# DisplayTestBoard.net
KiCad netlist of a schematic drawn in EAGLE
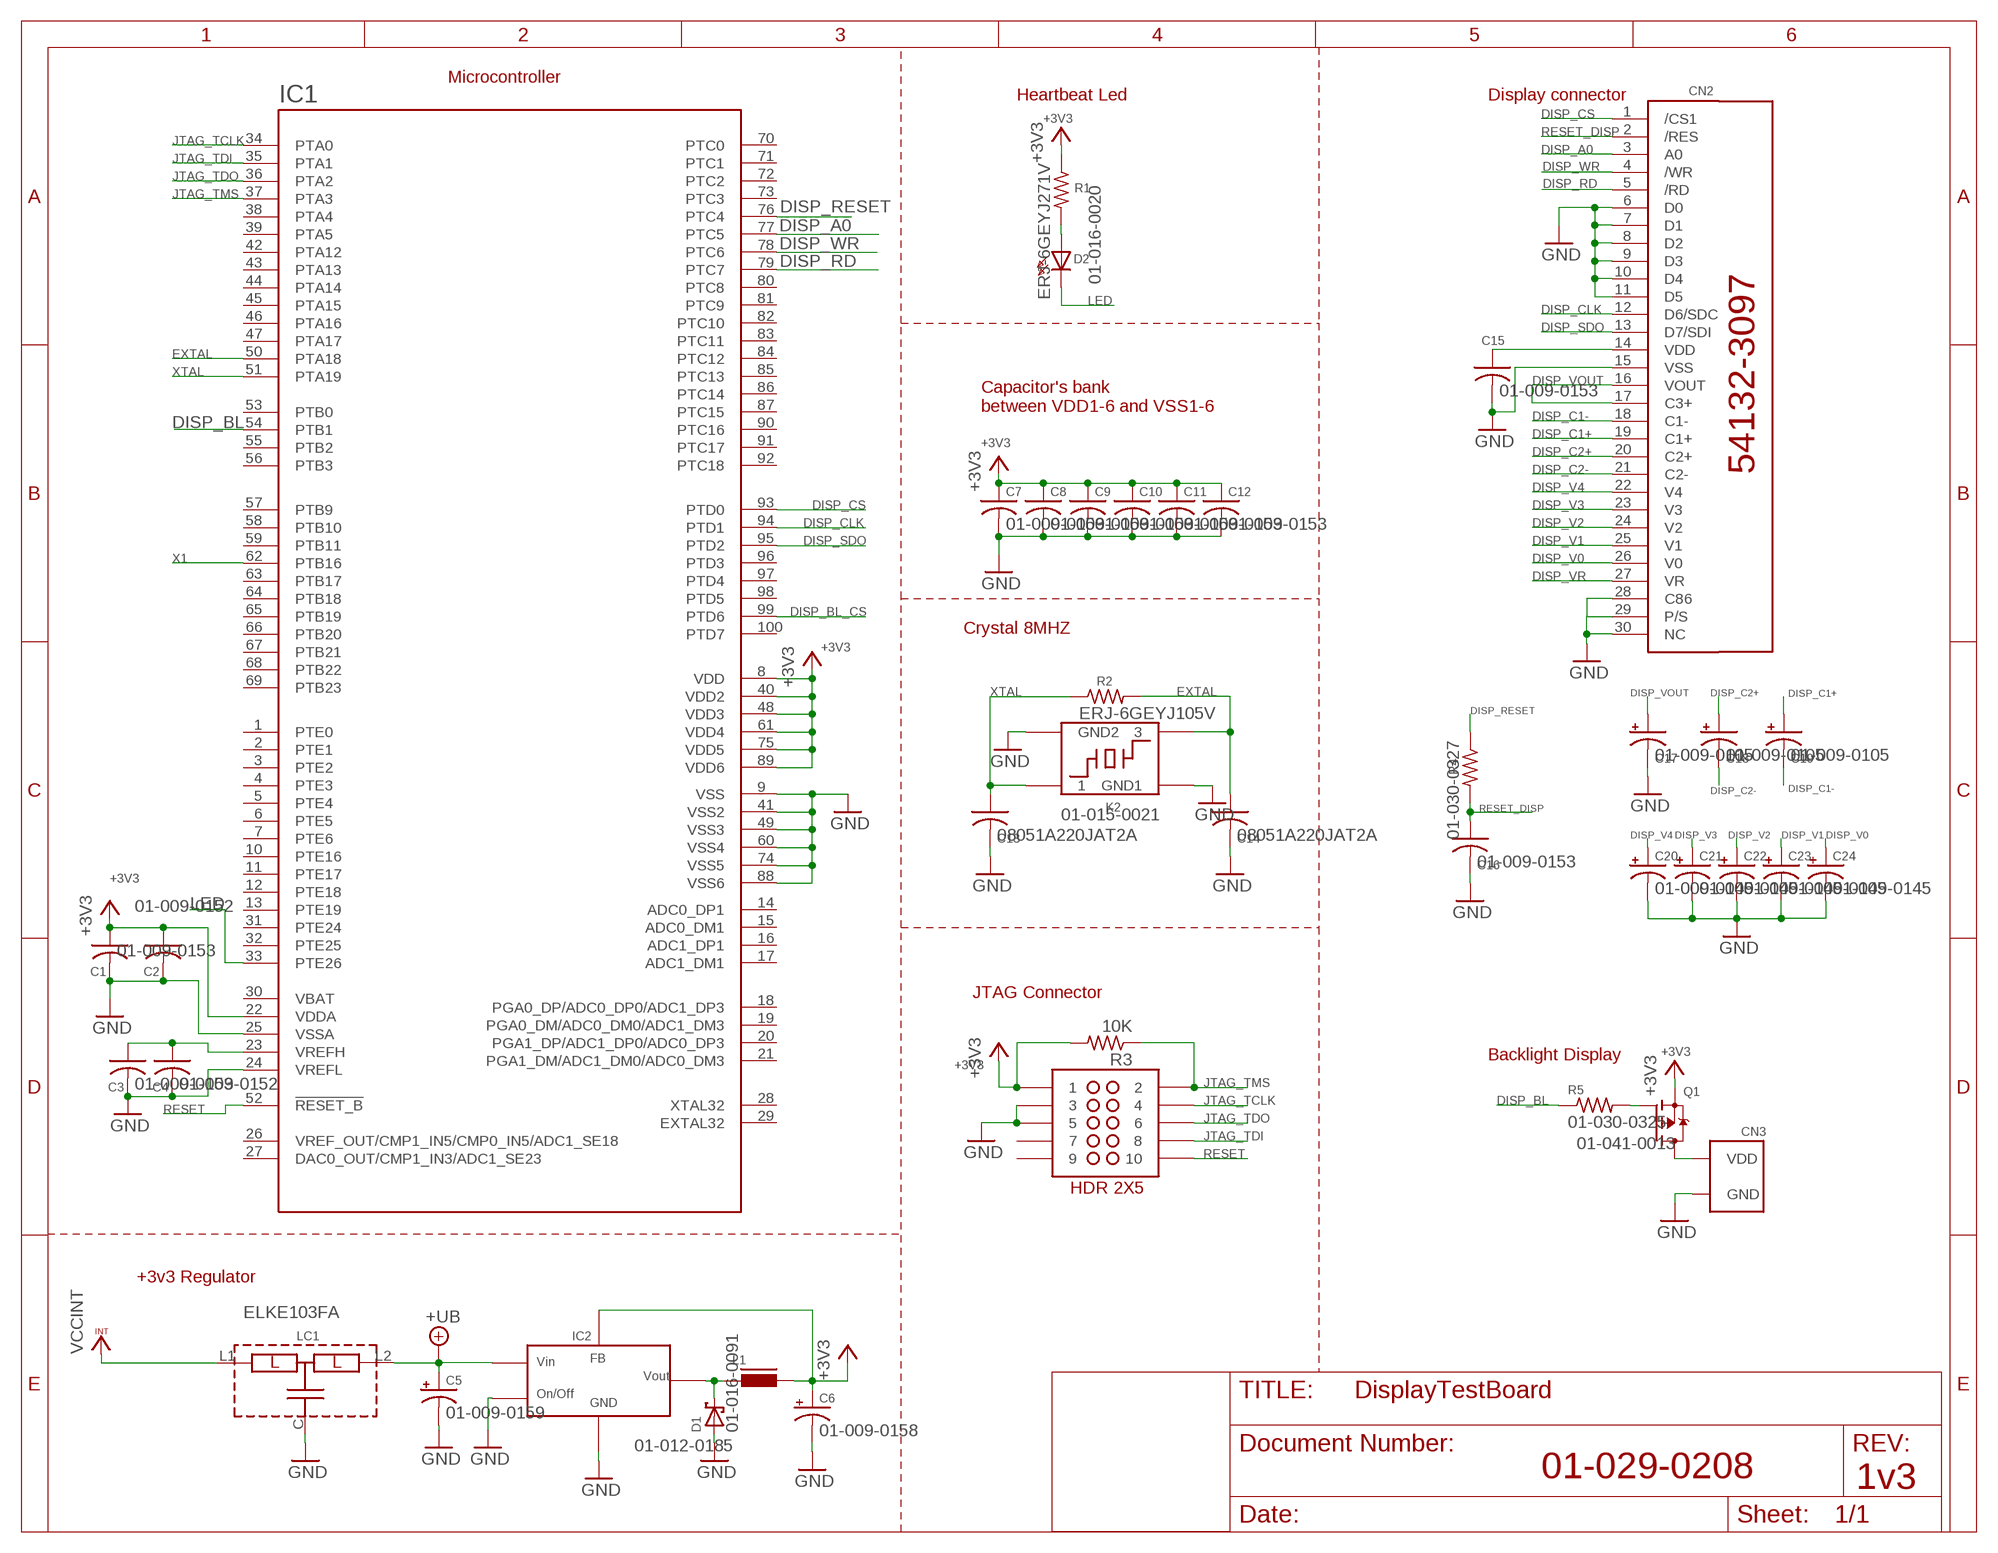
[diagram p0: schematic, sheet 1]

(export (version "E")
  (design (tool "Eeschema 10.0.6"))
  (components
    (comp (ref "C1")
      (value "01-009-0153")
      (footprint "eagle-import:C0805")
      (libsource (lib "eagle-import") (part "01-009-0153"))
    )
    (comp (ref "C2")
      (value "01-009-0152")
      (footprint "eagle-import:C0805")
      (libsource (lib "eagle-import") (part "01-009-0152"))
    )
    (comp (ref "C3")
      (value "01-009-0153")
      (footprint "eagle-import:C0805")
      (libsource (lib "eagle-import") (part "01-009-0153"))
    )
    (comp (ref "C4")
      (value "01-009-0152")
      (footprint "eagle-import:C0805")
      (libsource (lib "eagle-import") (part "01-009-0152"))
    )
    (comp (ref "C5")
      (value "01-009-0159")
      (footprint "eagle-import:PANASONIC_6.3MM")
      (libsource (lib "eagle-import") (part "01-009-0159"))
    )
    (comp (ref "C6")
      (value "01-009-0158")
      (footprint "eagle-import:PANASONIC_6.3MM")
      (libsource (lib "eagle-import") (part "01-009-0158"))
    )
    (comp (ref "C7")
      (value "01-009-0153")
      (footprint "eagle-import:C0805")
      (libsource (lib "eagle-import") (part "01-009-0153"))
    )
    (comp (ref "C8")
      (value "01-009-0153")
      (footprint "eagle-import:C0805")
      (libsource (lib "eagle-import") (part "01-009-0153"))
    )
    (comp (ref "C9")
      (value "01-009-0153")
      (footprint "eagle-import:C0805")
      (libsource (lib "eagle-import") (part "01-009-0153"))
    )
    (comp (ref "C10")
      (value "01-009-0153")
      (footprint "eagle-import:C0805")
      (libsource (lib "eagle-import") (part "01-009-0153"))
    )
    (comp (ref "C11")
      (value "01-009-0153")
      (footprint "eagle-import:C0805")
      (libsource (lib "eagle-import") (part "01-009-0153"))
    )
    (comp (ref "C12")
      (value "01-009-0153")
      (footprint "eagle-import:C0805")
      (libsource (lib "eagle-import") (part "01-009-0153"))
    )
    (comp (ref "C13")
      (value "08051A220JAT2A")
      (footprint "eagle-import:C0805")
      (libsource (lib "eagle-import") (part "08051A220JAT2A"))
    )
    (comp (ref "C14")
      (value "08051A220JAT2A")
      (footprint "eagle-import:C0805")
      (libsource (lib "eagle-import") (part "08051A220JAT2A"))
    )
    (comp (ref "C15")
      (value "01-009-0153")
      (footprint "eagle-import:C0805")
      (libsource (lib "eagle-import") (part "01-009-0153"))
    )
    (comp (ref "C16")
      (value "01-009-0153")
      (footprint "eagle-import:C0805")
      (libsource (lib "eagle-import") (part "01-009-0153"))
    )
    (comp (ref "C17")
      (value "01-009-0105")
      (footprint "eagle-import:CT3528")
      (libsource (lib "eagle-import") (part "01-009-0105"))
    )
    (comp (ref "C18")
      (value "01-009-0105")
      (footprint "eagle-import:CT3528")
      (libsource (lib "eagle-import") (part "01-009-0105"))
    )
    (comp (ref "C19")
      (value "01-009-0105")
      (footprint "eagle-import:CT3528")
      (libsource (lib "eagle-import") (part "01-009-0105"))
    )
    (comp (ref "C20")
      (value "01-009-0145")
      (footprint "eagle-import:CT3528")
      (libsource (lib "eagle-import") (part "01-009-0145"))
    )
    (comp (ref "C21")
      (value "01-009-0145")
      (footprint "eagle-import:CT3528")
      (libsource (lib "eagle-import") (part "01-009-0145"))
    )
    (comp (ref "C22")
      (value "01-009-0145")
      (footprint "eagle-import:CT3528")
      (libsource (lib "eagle-import") (part "01-009-0145"))
    )
    (comp (ref "C23")
      (value "01-009-0145")
      (footprint "eagle-import:CT3528")
      (libsource (lib "eagle-import") (part "01-009-0145"))
    )
    (comp (ref "C24")
      (value "01-009-0145")
      (footprint "eagle-import:CT3528")
      (libsource (lib "eagle-import") (part "01-009-0145"))
    )
    (comp (ref "CN2")
      (value "01-014-0371")
      (footprint "eagle-import:XF2L-3035-1")
      (libsource (lib "eagle-import") (part "01-014-0371"))
    )
    (comp (ref "CN3")
      (value "01-014-0372")
      (footprint "eagle-import:S2B-PH-K-S")
      (libsource (lib "eagle-import") (part "01-014-0372"))
    )
    (comp (ref "D1")
      (value "01-016-0091")
      (footprint "eagle-import:SOD123")
      (libsource (lib "eagle-import") (part "01-016-0091"))
    )
    (comp (ref "D2")
      (value "01-016-0020")
      (footprint "eagle-import:LED0603")
      (libsource (lib "eagle-import") (part "01-016-0020"))
    )
    (comp (ref "IC1")
      (value "01-012-0181")
      (footprint "eagle-import:LQFP100")
      (libsource (lib "eagle-import") (part "01-012-0181"))
    )
    (comp (ref "IC2")
      (value "01-012-0185")
      (footprint "eagle-import:SO08")
      (libsource (lib "eagle-import") (part "01-012-0185"))
    )
    (comp (ref "JTAG")
      (value "SAMTECSTR2X5")
      (footprint "eagle-import:SAMTECSTR2X5")
      (libsource (lib "eagle-import") (part "SAMTECSTR2X5"))
    )
    (comp (ref "K2")
      (value "01-015-0021")
      (footprint "eagle-import:XTAL")
      (libsource (lib "eagle-import") (part "01-015-0021"))
    )
    (comp (ref "L1")
      (value "01-023-0014")
      (footprint "eagle-import:SRR1260")
      (libsource (lib "eagle-import") (part "01-023-0014"))
    )
    (comp (ref "LC1")
      (value "ELKE103FA")
      (footprint "eagle-import:ELKE103FA")
      (libsource (lib "eagle-import") (part "ELKE103FA"))
    )
    (comp (ref "Q1")
      (value "01-041-0013")
      (footprint "eagle-import:SOT-23")
      (libsource (lib "eagle-import") (part "01-041-0013"))
    )
    (comp (ref "R1")
      (value "ERJ-6GEYJ271V")
      (footprint "eagle-import:M0805")
      (libsource (lib "eagle-import") (part "ERJ-6GEYJ271V"))
    )
    (comp (ref "R2")
      (value "ERJ-6GEYJ105V")
      (footprint "eagle-import:M0805")
      (libsource (lib "eagle-import") (part "ERJ-6GEYJ105V"))
    )
    (comp (ref "R3")
      (value "10K")
      (footprint "eagle-import:M0805")
      (libsource (lib "eagle-import") (part "01-030-0334"))
    )
    (comp (ref "R4")
      (value "01-030-0327")
      (footprint "eagle-import:M0805")
      (libsource (lib "eagle-import") (part "01-030-0327"))
    )
    (comp (ref "R5")
      (value "01-030-0325")
      (footprint "eagle-import:M0805")
      (libsource (lib "eagle-import") (part "01-030-0325"))
    )
  )
  (nets
    (net (code "1") (name "+3V3") (class "Default")
      (node (ref "C1") (pin "1") (pinfunction "1_1") (pintype "passive"))
      (node (ref "C10") (pin "1") (pinfunction "1_1") (pintype "passive"))
      (node (ref "C11") (pin "1") (pinfunction "1_1") (pintype "passive"))
      (node (ref "C12") (pin "1") (pinfunction "1_1") (pintype "passive"))
      (node (ref "C15") (pin "1") (pinfunction "1_1") (pintype "passive"))
      (node (ref "C2") (pin "1") (pinfunction "1_1") (pintype "passive"))
      (node (ref "C3") (pin "1") (pinfunction "1_1") (pintype "passive"))
      (node (ref "C4") (pin "1") (pinfunction "1_1") (pintype "passive"))
      (node (ref "C6") (pin "+") (pinfunction "+_+") (pintype "passive"))
      (node (ref "C7") (pin "1") (pinfunction "1_1") (pintype "passive"))
      (node (ref "C8") (pin "1") (pinfunction "1_1") (pintype "passive"))
      (node (ref "C9") (pin "1") (pinfunction "1_1") (pintype "passive"))
      (node (ref "CN2") (pin "14") (pinfunction "VDD_14") (pintype "bidirectional"))
      (node (ref "IC1") (pin "22") (pinfunction "VDDA_22") (pintype "bidirectional"))
      (node (ref "IC1") (pin "23") (pinfunction "VREFH_23") (pintype "bidirectional"))
      (node (ref "IC1") (pin "40") (pinfunction "VDD2_40") (pintype "bidirectional"))
      (node (ref "IC1") (pin "48") (pinfunction "VDD3_48") (pintype "bidirectional"))
      (node (ref "IC1") (pin "61") (pinfunction "VDD4_61") (pintype "bidirectional"))
      (node (ref "IC1") (pin "75") (pinfunction "VDD5_75") (pintype "bidirectional"))
      (node (ref "IC1") (pin "8") (pinfunction "VDD_8") (pintype "bidirectional"))
      (node (ref "IC1") (pin "89") (pinfunction "VDD6_89") (pintype "bidirectional"))
      (node (ref "IC2") (pin "4") (pinfunction "FB_4") (pintype "bidirectional"))
      (node (ref "JTAG") (pin "P$1") (pinfunction "1_P$1") (pintype "bidirectional"))
      (node (ref "L1") (pin "2") (pinfunction "2_2") (pintype "passive"))
      (node (ref "Q1") (pin "2") (pinfunction "S_2") (pintype "passive"))
      (node (ref "R1") (pin "1") (pinfunction "1_1") (pintype "passive"))
      (node (ref "R3") (pin "2") (pinfunction "2_2") (pintype "passive"))
    )
    (net (code "2") (name "+UB") (class "Default")
      (node (ref "C5") (pin "+") (pinfunction "+_+") (pintype "passive"))
      (node (ref "IC2") (pin "7") (pinfunction "VIN_7") (pintype "bidirectional"))
      (node (ref "LC1") (pin "L2") (pinfunction "L2_L2") (pintype "passive"))
    )
    (net (code "3") (name "/DISP_A0") (class "Default")
      (node (ref "CN2") (pin "3") (pinfunction "A0_3") (pintype "bidirectional"))
      (node (ref "IC1") (pin "77") (pinfunction "PTC5_77") (pintype "bidirectional"))
    )
    (net (code "4") (name "/DISP_BL") (class "Default")
      (node (ref "IC1") (pin "54") (pinfunction "PTB1_54") (pintype "bidirectional"))
      (node (ref "R5") (pin "1") (pinfunction "1_1") (pintype "passive"))
    )
    (net (code "5") (name "/DISP_BL_CS") (class "Default")
      (node (ref "IC1") (pin "99") (pinfunction "PTD6_99") (pintype "bidirectional"))
    )
    (net (code "6") (name "/DISP_C1+") (class "Default")
      (node (ref "C19") (pin "+") (pinfunction "+_+") (pintype "passive"))
      (node (ref "CN2") (pin "19") (pinfunction "C1+_19") (pintype "bidirectional"))
    )
    (net (code "7") (name "/DISP_C1-") (class "Default")
      (node (ref "C19") (pin "-") (pinfunction "-_-") (pintype "passive"))
      (node (ref "CN2") (pin "18") (pinfunction "C1-_18") (pintype "bidirectional"))
    )
    (net (code "8") (name "/DISP_C2+") (class "Default")
      (node (ref "C18") (pin "+") (pinfunction "+_+") (pintype "passive"))
      (node (ref "CN2") (pin "20") (pinfunction "C2+_20") (pintype "bidirectional"))
    )
    (net (code "9") (name "/DISP_C2-") (class "Default")
      (node (ref "C18") (pin "-") (pinfunction "-_-") (pintype "passive"))
      (node (ref "CN2") (pin "21") (pinfunction "C2-_21") (pintype "bidirectional"))
    )
    (net (code "10") (name "/DISP_CLK") (class "Default")
      (node (ref "CN2") (pin "12") (pinfunction "D6/SDC_12") (pintype "bidirectional"))
      (node (ref "IC1") (pin "94") (pinfunction "PTD1_94") (pintype "bidirectional"))
    )
    (net (code "11") (name "/DISP_CS") (class "Default")
      (node (ref "CN2") (pin "1") (pinfunction "/CS1_1") (pintype "bidirectional"))
      (node (ref "IC1") (pin "93") (pinfunction "PTD0_93") (pintype "bidirectional"))
    )
    (net (code "12") (name "/DISP_RD") (class "Default")
      (node (ref "CN2") (pin "5") (pinfunction "/RD_5") (pintype "bidirectional"))
      (node (ref "IC1") (pin "79") (pinfunction "PTC7_79") (pintype "bidirectional"))
    )
    (net (code "13") (name "/DISP_RESET") (class "Default")
      (node (ref "IC1") (pin "76") (pinfunction "PTC4_76") (pintype "bidirectional"))
      (node (ref "R4") (pin "1") (pinfunction "1_1") (pintype "passive"))
    )
    (net (code "14") (name "/DISP_SDO") (class "Default")
      (node (ref "CN2") (pin "13") (pinfunction "D7/SDI_13") (pintype "bidirectional"))
      (node (ref "IC1") (pin "95") (pinfunction "PTD2_95") (pintype "bidirectional"))
    )
    (net (code "15") (name "/DISP_V0") (class "Default")
      (node (ref "C24") (pin "+") (pinfunction "+_+") (pintype "passive"))
      (node (ref "CN2") (pin "26") (pinfunction "V0_26") (pintype "bidirectional"))
    )
    (net (code "16") (name "/DISP_V1") (class "Default")
      (node (ref "C23") (pin "+") (pinfunction "+_+") (pintype "passive"))
      (node (ref "CN2") (pin "25") (pinfunction "V1_25") (pintype "bidirectional"))
    )
    (net (code "17") (name "/DISP_V2") (class "Default")
      (node (ref "C22") (pin "+") (pinfunction "+_+") (pintype "passive"))
      (node (ref "CN2") (pin "24") (pinfunction "V2_24") (pintype "bidirectional"))
    )
    (net (code "18") (name "/DISP_V3") (class "Default")
      (node (ref "C21") (pin "+") (pinfunction "+_+") (pintype "passive"))
      (node (ref "CN2") (pin "23") (pinfunction "V3_23") (pintype "bidirectional"))
    )
    (net (code "19") (name "/DISP_V4") (class "Default")
      (node (ref "C20") (pin "+") (pinfunction "+_+") (pintype "passive"))
      (node (ref "CN2") (pin "22") (pinfunction "V4_22") (pintype "bidirectional"))
    )
    (net (code "20") (name "/DISP_VOUT") (class "Default")
      (node (ref "C17") (pin "+") (pinfunction "+_+") (pintype "passive"))
      (node (ref "CN2") (pin "16") (pinfunction "VOUT_16") (pintype "bidirectional"))
      (node (ref "CN2") (pin "17") (pinfunction "C3+_17") (pintype "bidirectional"))
    )
    (net (code "21") (name "/DISP_VR") (class "Default")
      (node (ref "CN2") (pin "27") (pinfunction "VR_27") (pintype "bidirectional"))
    )
    (net (code "22") (name "/DISP_WR") (class "Default")
      (node (ref "CN2") (pin "4") (pinfunction "/WR_4") (pintype "bidirectional"))
      (node (ref "IC1") (pin "78") (pinfunction "PTC6_78") (pintype "bidirectional"))
    )
    (net (code "23") (name "/EXTAL") (class "Default")
      (node (ref "C14") (pin "1") (pinfunction "1_1") (pintype "passive"))
      (node (ref "IC1") (pin "50") (pinfunction "PTA18_50") (pintype "bidirectional"))
      (node (ref "K2") (pin "P$3") (pinfunction "3_P$3") (pintype "bidirectional"))
      (node (ref "R2") (pin "2") (pinfunction "2_2") (pintype "passive"))
    )
    (net (code "24") (name "/JTAG_TCLK") (class "Default")
      (node (ref "IC1") (pin "34") (pinfunction "PTA0_34") (pintype "bidirectional"))
      (node (ref "JTAG") (pin "P$7") (pinfunction "4_P$7") (pintype "bidirectional"))
    )
    (net (code "25") (name "/JTAG_TDI") (class "Default")
      (node (ref "IC1") (pin "35") (pinfunction "PTA1_35") (pintype "bidirectional"))
      (node (ref "JTAG") (pin "P$9") (pinfunction "8_P$9") (pintype "bidirectional"))
    )
    (net (code "26") (name "/JTAG_TDO") (class "Default")
      (node (ref "IC1") (pin "36") (pinfunction "PTA2_36") (pintype "bidirectional"))
      (node (ref "JTAG") (pin "P$8") (pinfunction "6_P$8") (pintype "bidirectional"))
    )
    (net (code "27") (name "/JTAG_TMS") (class "Default")
      (node (ref "IC1") (pin "37") (pinfunction "PTA3_37") (pintype "bidirectional"))
      (node (ref "JTAG") (pin "P$6") (pinfunction "2_P$6") (pintype "bidirectional"))
      (node (ref "R3") (pin "1") (pinfunction "1_1") (pintype "passive"))
    )
    (net (code "28") (name "/LED") (class "Default")
      (node (ref "D2") (pin "K") (pinfunction "C_K") (pintype "passive"))
      (node (ref "IC1") (pin "33") (pinfunction "PTE26_33") (pintype "bidirectional"))
    )
    (net (code "29") (name "/RESET") (class "Default")
      (node (ref "IC1") (pin "52") (pinfunction "~{RESET_B}_52") (pintype "bidirectional"))
      (node (ref "JTAG") (pin "P$10") (pinfunction "10_P$10") (pintype "bidirectional"))
    )
    (net (code "30") (name "/RESET_DISP") (class "Default")
      (node (ref "C16") (pin "1") (pinfunction "1_1") (pintype "passive"))
      (node (ref "CN2") (pin "2") (pinfunction "/RES_2") (pintype "bidirectional"))
      (node (ref "R4") (pin "2") (pinfunction "2_2") (pintype "passive"))
    )
    (net (code "31") (name "/X1") (class "Default")
      (node (ref "IC1") (pin "62") (pinfunction "PTB16_62") (pintype "bidirectional"))
    )
    (net (code "32") (name "/XTAL") (class "Default")
      (node (ref "C13") (pin "1") (pinfunction "1_1") (pintype "passive"))
      (node (ref "IC1") (pin "51") (pinfunction "PTA19_51") (pintype "bidirectional"))
      (node (ref "K2") (pin "P$1") (pinfunction "1_P$1") (pintype "bidirectional"))
      (node (ref "R2") (pin "1") (pinfunction "1_1") (pintype "passive"))
    )
    (net (code "33") (name "GND") (class "Default")
      (node (ref "C1") (pin "2") (pinfunction "2_2") (pintype "passive"))
      (node (ref "C10") (pin "2") (pinfunction "2_2") (pintype "passive"))
      (node (ref "C11") (pin "2") (pinfunction "2_2") (pintype "passive"))
      (node (ref "C12") (pin "2") (pinfunction "2_2") (pintype "passive"))
      (node (ref "C13") (pin "2") (pinfunction "2_2") (pintype "passive"))
      (node (ref "C14") (pin "2") (pinfunction "2_2") (pintype "passive"))
      (node (ref "C15") (pin "2") (pinfunction "2_2") (pintype "passive"))
      (node (ref "C16") (pin "2") (pinfunction "2_2") (pintype "passive"))
      (node (ref "C17") (pin "-") (pinfunction "-_-") (pintype "passive"))
      (node (ref "C2") (pin "2") (pinfunction "2_2") (pintype "passive"))
      (node (ref "C20") (pin "-") (pinfunction "-_-") (pintype "passive"))
      (node (ref "C21") (pin "-") (pinfunction "-_-") (pintype "passive"))
      (node (ref "C22") (pin "-") (pinfunction "-_-") (pintype "passive"))
      (node (ref "C23") (pin "-") (pinfunction "-_-") (pintype "passive"))
      (node (ref "C24") (pin "-") (pinfunction "-_-") (pintype "passive"))
      (node (ref "C3") (pin "2") (pinfunction "2_2") (pintype "passive"))
      (node (ref "C4") (pin "2") (pinfunction "2_2") (pintype "passive"))
      (node (ref "C5") (pin "-") (pinfunction "-_-") (pintype "passive"))
      (node (ref "C6") (pin "-") (pinfunction "-_-") (pintype "passive"))
      (node (ref "C7") (pin "2") (pinfunction "2_2") (pintype "passive"))
      (node (ref "C8") (pin "2") (pinfunction "2_2") (pintype "passive"))
      (node (ref "C9") (pin "2") (pinfunction "2_2") (pintype "passive"))
      (node (ref "CN2") (pin "10") (pinfunction "D4_10") (pintype "bidirectional"))
      (node (ref "CN2") (pin "11") (pinfunction "D5_11") (pintype "bidirectional"))
      (node (ref "CN2") (pin "15") (pinfunction "VSS_15") (pintype "bidirectional"))
      (node (ref "CN2") (pin "28") (pinfunction "C86_28") (pintype "bidirectional"))
      (node (ref "CN2") (pin "29") (pinfunction "P/S_29") (pintype "bidirectional"))
      (node (ref "CN2") (pin "30") (pinfunction "NC_30") (pintype "bidirectional"))
      (node (ref "CN2") (pin "6") (pinfunction "D0_6") (pintype "bidirectional"))
      (node (ref "CN2") (pin "7") (pinfunction "D1_7") (pintype "bidirectional"))
      (node (ref "CN2") (pin "8") (pinfunction "D2_8") (pintype "bidirectional"))
      (node (ref "CN2") (pin "9") (pinfunction "D3_9") (pintype "bidirectional"))
      (node (ref "CN3") (pin "GND") (pinfunction "GND_GND") (pintype "bidirectional"))
      (node (ref "D1") (pin "A") (pinfunction "A_A") (pintype "passive"))
      (node (ref "IC1") (pin "24") (pinfunction "VREFL_24") (pintype "bidirectional"))
      (node (ref "IC1") (pin "25") (pinfunction "VSSA_25") (pintype "bidirectional"))
      (node (ref "IC1") (pin "41") (pinfunction "VSS2_41") (pintype "bidirectional"))
      (node (ref "IC1") (pin "49") (pinfunction "VSS3_49") (pintype "bidirectional"))
      (node (ref "IC1") (pin "60") (pinfunction "VSS4_60") (pintype "bidirectional"))
      (node (ref "IC1") (pin "74") (pinfunction "VSS5_74") (pintype "bidirectional"))
      (node (ref "IC1") (pin "88") (pinfunction "VSS6_88") (pintype "bidirectional"))
      (node (ref "IC1") (pin "9") (pinfunction "VSS_9") (pintype "bidirectional"))
      (node (ref "IC2") (pin "5") (pinfunction "ON/OFF_5") (pintype "bidirectional"))
      (node (ref "IC2") (pin "6") (pinfunction "GND_6") (pintype "bidirectional"))
      (node (ref "JTAG") (pin "P$2") (pinfunction "3_P$2") (pintype "bidirectional"))
      (node (ref "JTAG") (pin "P$3") (pinfunction "5_P$3") (pintype "bidirectional"))
      (node (ref "K2") (pin "P$2") (pinfunction "GND1_P$2") (pintype "bidirectional"))
      (node (ref "K2") (pin "P$4") (pinfunction "GND2_P$4") (pintype "bidirectional"))
      (node (ref "LC1") (pin "C") (pinfunction "C_C") (pintype "passive"))
    )
    (net (code "34") (name "Net-(D2-PadA)") (class "Default")
      (node (ref "D2") (pin "A") (pinfunction "A_A") (pintype "passive"))
      (node (ref "R1") (pin "2") (pinfunction "2_2") (pintype "passive"))
    )
    (net (code "35") (name "Net-(IC2-VOUT)") (class "Default")
      (node (ref "D1") (pin "C") (pinfunction "C_C") (pintype "passive"))
      (node (ref "IC2") (pin "8") (pinfunction "VOUT_8") (pintype "bidirectional"))
      (node (ref "L1") (pin "1") (pinfunction "1_1") (pintype "passive"))
    )
    (net (code "36") (name "Net-(Q1-D)") (class "Default")
      (node (ref "CN3") (pin "VDD") (pinfunction "VDD_VDD") (pintype "bidirectional"))
      (node (ref "Q1") (pin "3") (pinfunction "D_3") (pintype "passive"))
    )
    (net (code "37") (name "Net-(Q1-G)") (class "Default")
      (node (ref "Q1") (pin "1") (pinfunction "G_1") (pintype "passive"))
      (node (ref "R5") (pin "2") (pinfunction "2_2") (pintype "passive"))
    )
    (net (code "38") (name "VCCINT") (class "Default")
      (node (ref "LC1") (pin "L1") (pinfunction "L1_L1") (pintype "passive"))
    )
    (net (code "39") (name "unconnected-(IC1-ADC0_DM1-Pad15)") (class "Default")
      (node (ref "IC1") (pin "15") (pinfunction "ADC0_DM1_15") (pintype "bidirectional"))
    )
    (net (code "40") (name "unconnected-(IC1-ADC0_DP1-Pad14)") (class "Default")
      (node (ref "IC1") (pin "14") (pinfunction "ADC0_DP1_14") (pintype "bidirectional"))
    )
    (net (code "41") (name "unconnected-(IC1-ADC1_DM1-Pad17)") (class "Default")
      (node (ref "IC1") (pin "17") (pinfunction "ADC1_DM1_17") (pintype "bidirectional"))
    )
    (net (code "42") (name "unconnected-(IC1-ADC1_DP1-Pad16)") (class "Default")
      (node (ref "IC1") (pin "16") (pinfunction "ADC1_DP1_16") (pintype "bidirectional"))
    )
    (net (code "43") (name "unconnected-(IC1-DAC0_OUT{slash}CMP1_IN3{slash}ADC1_SE23-Pad27)") (class "Default")
      (node (ref "IC1") (pin "27") (pinfunction "DAC0_OUT/CMP1_IN3/ADC1_SE23_27") (pintype "bidirectional"))
    )
    (net (code "44") (name "unconnected-(IC1-EXTAL32-Pad29)") (class "Default")
      (node (ref "IC1") (pin "29") (pinfunction "EXTAL32_29") (pintype "bidirectional"))
    )
    (net (code "45") (name "unconnected-(IC1-PGA0_DM{slash}ADC0_DM0{slash}ADC1_DM3-Pad19)") (class "Default")
      (node (ref "IC1") (pin "19") (pinfunction "PGA0_DM/ADC0_DM0/ADC1_DM3_19") (pintype "bidirectional"))
    )
    (net (code "46") (name "unconnected-(IC1-PGA0_DP{slash}ADC0_DP0{slash}ADC1_DP3-Pad18)") (class "Default")
      (node (ref "IC1") (pin "18") (pinfunction "PGA0_DP/ADC0_DP0/ADC1_DP3_18") (pintype "bidirectional"))
    )
    (net (code "47") (name "unconnected-(IC1-PGA1_DM{slash}ADC1_DM0{slash}ADC0_DM3-Pad21)") (class "Default")
      (node (ref "IC1") (pin "21") (pinfunction "PGA1_DM/ADC1_DM0/ADC0_DM3_21") (pintype "bidirectional"))
    )
    (net (code "48") (name "unconnected-(IC1-PGA1_DP{slash}ADC1_DP0{slash}ADC0_DP3-Pad20)") (class "Default")
      (node (ref "IC1") (pin "20") (pinfunction "PGA1_DP/ADC1_DP0/ADC0_DP3_20") (pintype "bidirectional"))
    )
    (net (code "49") (name "unconnected-(IC1-PTA4-Pad38)") (class "Default")
      (node (ref "IC1") (pin "38") (pinfunction "PTA4_38") (pintype "bidirectional"))
    )
    (net (code "50") (name "unconnected-(IC1-PTA5-Pad39)") (class "Default")
      (node (ref "IC1") (pin "39") (pinfunction "PTA5_39") (pintype "bidirectional"))
    )
    (net (code "51") (name "unconnected-(IC1-PTA12-Pad42)") (class "Default")
      (node (ref "IC1") (pin "42") (pinfunction "PTA12_42") (pintype "bidirectional"))
    )
    (net (code "52") (name "unconnected-(IC1-PTA13-Pad43)") (class "Default")
      (node (ref "IC1") (pin "43") (pinfunction "PTA13_43") (pintype "bidirectional"))
    )
    (net (code "53") (name "unconnected-(IC1-PTA14-Pad44)") (class "Default")
      (node (ref "IC1") (pin "44") (pinfunction "PTA14_44") (pintype "bidirectional"))
    )
    (net (code "54") (name "unconnected-(IC1-PTA15-Pad45)") (class "Default")
      (node (ref "IC1") (pin "45") (pinfunction "PTA15_45") (pintype "bidirectional"))
    )
    (net (code "55") (name "unconnected-(IC1-PTA16-Pad46)") (class "Default")
      (node (ref "IC1") (pin "46") (pinfunction "PTA16_46") (pintype "bidirectional"))
    )
    (net (code "56") (name "unconnected-(IC1-PTA17-Pad47)") (class "Default")
      (node (ref "IC1") (pin "47") (pinfunction "PTA17_47") (pintype "bidirectional"))
    )
    (net (code "57") (name "unconnected-(IC1-PTB0-Pad53)") (class "Default")
      (node (ref "IC1") (pin "53") (pinfunction "PTB0_53") (pintype "bidirectional"))
    )
    (net (code "58") (name "unconnected-(IC1-PTB2-Pad55)") (class "Default")
      (node (ref "IC1") (pin "55") (pinfunction "PTB2_55") (pintype "bidirectional"))
    )
    (net (code "59") (name "unconnected-(IC1-PTB3-Pad56)") (class "Default")
      (node (ref "IC1") (pin "56") (pinfunction "PTB3_56") (pintype "bidirectional"))
    )
    (net (code "60") (name "unconnected-(IC1-PTB9-Pad57)") (class "Default")
      (node (ref "IC1") (pin "57") (pinfunction "PTB9_57") (pintype "bidirectional"))
    )
    (net (code "61") (name "unconnected-(IC1-PTB10-Pad58)") (class "Default")
      (node (ref "IC1") (pin "58") (pinfunction "PTB10_58") (pintype "bidirectional"))
    )
    (net (code "62") (name "unconnected-(IC1-PTB11-Pad59)") (class "Default")
      (node (ref "IC1") (pin "59") (pinfunction "PTB11_59") (pintype "bidirectional"))
    )
    (net (code "63") (name "unconnected-(IC1-PTB17-Pad63)") (class "Default")
      (node (ref "IC1") (pin "63") (pinfunction "PTB17_63") (pintype "bidirectional"))
    )
    (net (code "64") (name "unconnected-(IC1-PTB18-Pad64)") (class "Default")
      (node (ref "IC1") (pin "64") (pinfunction "PTB18_64") (pintype "bidirectional"))
    )
    (net (code "65") (name "unconnected-(IC1-PTB19-Pad65)") (class "Default")
      (node (ref "IC1") (pin "65") (pinfunction "PTB19_65") (pintype "bidirectional"))
    )
    (net (code "66") (name "unconnected-(IC1-PTB20-Pad66)") (class "Default")
      (node (ref "IC1") (pin "66") (pinfunction "PTB20_66") (pintype "bidirectional"))
    )
    (net (code "67") (name "unconnected-(IC1-PTB21-Pad67)") (class "Default")
      (node (ref "IC1") (pin "67") (pinfunction "PTB21_67") (pintype "bidirectional"))
    )
    (net (code "68") (name "unconnected-(IC1-PTB22-Pad68)") (class "Default")
      (node (ref "IC1") (pin "68") (pinfunction "PTB22_68") (pintype "bidirectional"))
    )
    (net (code "69") (name "unconnected-(IC1-PTB23-Pad69)") (class "Default")
      (node (ref "IC1") (pin "69") (pinfunction "PTB23_69") (pintype "bidirectional"))
    )
    (net (code "70") (name "unconnected-(IC1-PTC0-Pad70)") (class "Default")
      (node (ref "IC1") (pin "70") (pinfunction "PTC0_70") (pintype "bidirectional"))
    )
    (net (code "71") (name "unconnected-(IC1-PTC1-Pad71)") (class "Default")
      (node (ref "IC1") (pin "71") (pinfunction "PTC1_71") (pintype "bidirectional"))
    )
    (net (code "72") (name "unconnected-(IC1-PTC2-Pad72)") (class "Default")
      (node (ref "IC1") (pin "72") (pinfunction "PTC2_72") (pintype "bidirectional"))
    )
    (net (code "73") (name "unconnected-(IC1-PTC3-Pad73)") (class "Default")
      (node (ref "IC1") (pin "73") (pinfunction "PTC3_73") (pintype "bidirectional"))
    )
    (net (code "74") (name "unconnected-(IC1-PTC8-Pad80)") (class "Default")
      (node (ref "IC1") (pin "80") (pinfunction "PTC8_80") (pintype "bidirectional"))
    )
    (net (code "75") (name "unconnected-(IC1-PTC9-Pad81)") (class "Default")
      (node (ref "IC1") (pin "81") (pinfunction "PTC9_81") (pintype "bidirectional"))
    )
    (net (code "76") (name "unconnected-(IC1-PTC10-Pad82)") (class "Default")
      (node (ref "IC1") (pin "82") (pinfunction "PTC10_82") (pintype "bidirectional"))
    )
    (net (code "77") (name "unconnected-(IC1-PTC11-Pad83)") (class "Default")
      (node (ref "IC1") (pin "83") (pinfunction "PTC11_83") (pintype "bidirectional"))
    )
    (net (code "78") (name "unconnected-(IC1-PTC12-Pad84)") (class "Default")
      (node (ref "IC1") (pin "84") (pinfunction "PTC12_84") (pintype "bidirectional"))
    )
    (net (code "79") (name "unconnected-(IC1-PTC13-Pad85)") (class "Default")
      (node (ref "IC1") (pin "85") (pinfunction "PTC13_85") (pintype "bidirectional"))
    )
    (net (code "80") (name "unconnected-(IC1-PTC14-Pad86)") (class "Default")
      (node (ref "IC1") (pin "86") (pinfunction "PTC14_86") (pintype "bidirectional"))
    )
    (net (code "81") (name "unconnected-(IC1-PTC15-Pad87)") (class "Default")
      (node (ref "IC1") (pin "87") (pinfunction "PTC15_87") (pintype "bidirectional"))
    )
    (net (code "82") (name "unconnected-(IC1-PTC16-Pad90)") (class "Default")
      (node (ref "IC1") (pin "90") (pinfunction "PTC16_90") (pintype "bidirectional"))
    )
    (net (code "83") (name "unconnected-(IC1-PTC17-Pad91)") (class "Default")
      (node (ref "IC1") (pin "91") (pinfunction "PTC17_91") (pintype "bidirectional"))
    )
    (net (code "84") (name "unconnected-(IC1-PTC18-Pad92)") (class "Default")
      (node (ref "IC1") (pin "92") (pinfunction "PTC18_92") (pintype "bidirectional"))
    )
    (net (code "85") (name "unconnected-(IC1-PTD3-Pad96)") (class "Default")
      (node (ref "IC1") (pin "96") (pinfunction "PTD3_96") (pintype "bidirectional"))
    )
    (net (code "86") (name "unconnected-(IC1-PTD4-Pad97)") (class "Default")
      (node (ref "IC1") (pin "97") (pinfunction "PTD4_97") (pintype "bidirectional"))
    )
    (net (code "87") (name "unconnected-(IC1-PTD5-Pad98)") (class "Default")
      (node (ref "IC1") (pin "98") (pinfunction "PTD5_98") (pintype "bidirectional"))
    )
    (net (code "88") (name "unconnected-(IC1-PTD7-Pad100)") (class "Default")
      (node (ref "IC1") (pin "100") (pinfunction "PTD7_100") (pintype "bidirectional"))
    )
    (net (code "89") (name "unconnected-(IC1-PTE0-Pad1)") (class "Default")
      (node (ref "IC1") (pin "1") (pinfunction "PTE0_1") (pintype "bidirectional"))
    )
    (net (code "90") (name "unconnected-(IC1-PTE1-Pad2)") (class "Default")
      (node (ref "IC1") (pin "2") (pinfunction "PTE1_2") (pintype "bidirectional"))
    )
    (net (code "91") (name "unconnected-(IC1-PTE2-Pad3)") (class "Default")
      (node (ref "IC1") (pin "3") (pinfunction "PTE2_3") (pintype "bidirectional"))
    )
    (net (code "92") (name "unconnected-(IC1-PTE3-Pad4)") (class "Default")
      (node (ref "IC1") (pin "4") (pinfunction "PTE3_4") (pintype "bidirectional"))
    )
    (net (code "93") (name "unconnected-(IC1-PTE4-Pad5)") (class "Default")
      (node (ref "IC1") (pin "5") (pinfunction "PTE4_5") (pintype "bidirectional"))
    )
    (net (code "94") (name "unconnected-(IC1-PTE5-Pad6)") (class "Default")
      (node (ref "IC1") (pin "6") (pinfunction "PTE5_6") (pintype "bidirectional"))
    )
    (net (code "95") (name "unconnected-(IC1-PTE6-Pad7)") (class "Default")
      (node (ref "IC1") (pin "7") (pinfunction "PTE6_7") (pintype "bidirectional"))
    )
    (net (code "96") (name "unconnected-(IC1-PTE16-Pad10)") (class "Default")
      (node (ref "IC1") (pin "10") (pinfunction "PTE16_10") (pintype "bidirectional"))
    )
    (net (code "97") (name "unconnected-(IC1-PTE17-Pad11)") (class "Default")
      (node (ref "IC1") (pin "11") (pinfunction "PTE17_11") (pintype "bidirectional"))
    )
    (net (code "98") (name "unconnected-(IC1-PTE18-Pad12)") (class "Default")
      (node (ref "IC1") (pin "12") (pinfunction "PTE18_12") (pintype "bidirectional"))
    )
    (net (code "99") (name "unconnected-(IC1-PTE19-Pad13)") (class "Default")
      (node (ref "IC1") (pin "13") (pinfunction "PTE19_13") (pintype "bidirectional"))
    )
    (net (code "100") (name "unconnected-(IC1-PTE24-Pad31)") (class "Default")
      (node (ref "IC1") (pin "31") (pinfunction "PTE24_31") (pintype "bidirectional"))
    )
    (net (code "101") (name "unconnected-(IC1-PTE25-Pad32)") (class "Default")
      (node (ref "IC1") (pin "32") (pinfunction "PTE25_32") (pintype "bidirectional"))
    )
    (net (code "102") (name "unconnected-(IC1-VBAT-Pad30)") (class "Default")
      (node (ref "IC1") (pin "30") (pinfunction "VBAT_30") (pintype "bidirectional"))
    )
    (net (code "103") (name "unconnected-(IC1-VREF_OUT{slash}CMP1_IN5{slash}CMP0_IN5{slash}ADC1_SE18-Pad26)") (class "Default")
      (node (ref "IC1") (pin "26") (pinfunction "VREF_OUT/CMP1_IN5/CMP0_IN5/ADC1_SE18_26") (pintype "bidirectional"))
    )
    (net (code "104") (name "unconnected-(IC1-XTAL32-Pad28)") (class "Default")
      (node (ref "IC1") (pin "28") (pinfunction "XTAL32_28") (pintype "bidirectional"))
    )
    (net (code "105") (name "unconnected-(JTAG-7-PadP$4)") (class "Default")
      (node (ref "JTAG") (pin "P$4") (pinfunction "7_P$4") (pintype "bidirectional"))
    )
    (net (code "106") (name "unconnected-(JTAG-9-PadP$5)") (class "Default")
      (node (ref "JTAG") (pin "P$5") (pinfunction "9_P$5") (pintype "bidirectional"))
    )
  )
)
